# Sheet1.net
KiCad netlist of a schematic drawn in Altium Designer
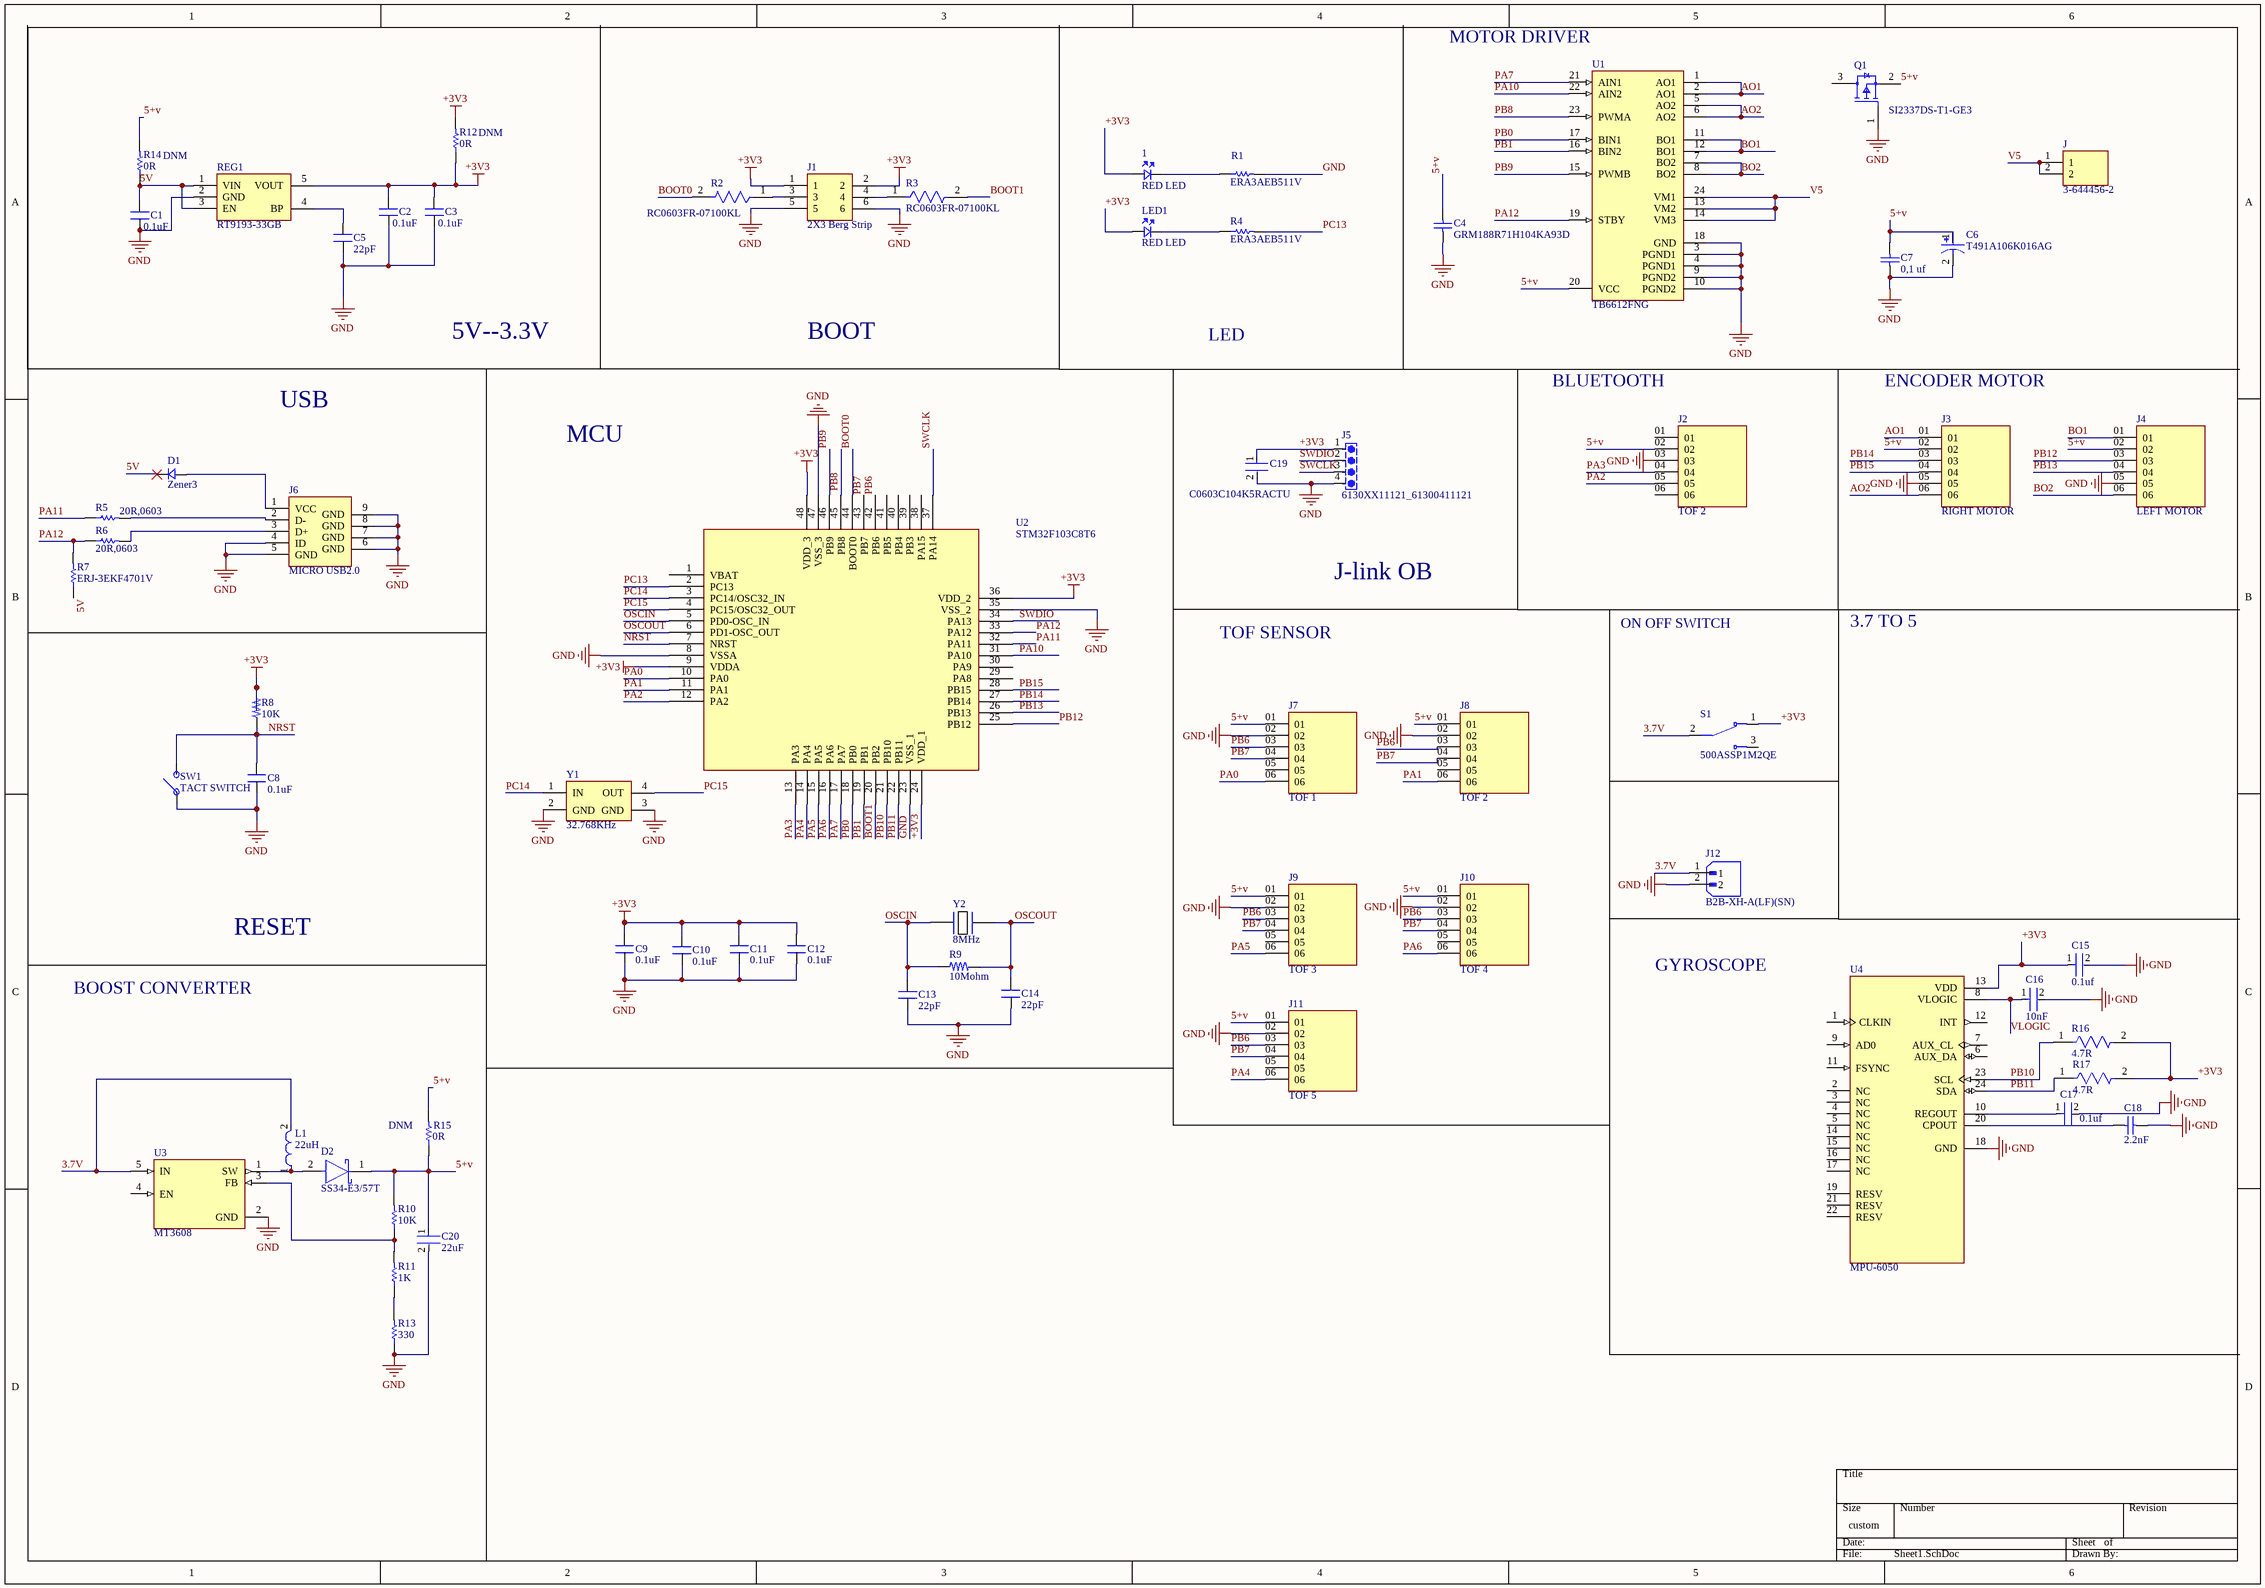
[diagram p0: Sheet1.SchDoc]

(export (version "E")
  (design (tool "Eeschema 10.0.6"))
  (components
    (comp (ref "1")
      (value "RED LED")
      (footprint "LED_0805")
      (description "Red 621nm LED Indication - Discrete 2V 0805 (2012 Metric)")
      (fields
        (field (name "MANUFACTURER") "Lite-On Inc.")
        (field (name "MANUFACTURER PART NUMBER") "LTST-C170EKT")
      )
      (libsource (lib "Schlib1") (part "LED-RED_10mA-0805"))
    )
    (comp (ref "C1")
      (value "0.1uF")
      (footprint "CAP_0805")
      (description "0.1µF ±5% 50V Ceramic Capacitor X7R 0805 (2012 Metric)")
      (fields
        (field (name "MANUFACTURER") "KEMET")
        (field (name "MANUFACTURING PART NUMBER") "C0805C104J5RACTU")
      )
      (libsource (lib "Schlib1") (part "CAP_0.1uF-50V-5%-0805"))
    )
    (comp (ref "C2")
      (value "0.1uF")
      (footprint "CAP_0805")
      (description "0.1µF ±5% 50V Ceramic Capacitor X7R 0805 (2012 Metric)")
      (fields
        (field (name "MANUFACTURER") "KEMET")
        (field (name "MANUFACTURING PART NUMBER") "C0805C104J5RACTU")
      )
      (libsource (lib "Schlib1") (part "CAP_0.1uF-50V-5%-0805"))
    )
    (comp (ref "C3")
      (value "0.1uF")
      (footprint "CAP_0805")
      (description "0.1µF ±5% 50V Ceramic Capacitor X7R 0805 (2012 Metric)")
      (fields
        (field (name "MANUFACTURER") "KEMET")
        (field (name "MANUFACTURING PART NUMBER") "C0805C104J5RACTU")
      )
      (libsource (lib "Schlib1") (part "CAP_0.1uF-50V-5%-0805"))
    )
    (comp (ref "C4")
      (value "GRM188R71H104KA93D")
      (footprint "CAPC1608X90X35ML10T15")
      (description "Chip Capacitor, 0.1 uF, +/- 10%, 50 V, -55 to 125 degC, 0603 (1608 Metric), RoHS, Tape and Reel")
      (fields (field (name "TOLERANCE") "10%") (field (name "VOLTAGE") "50V"))
      (libsource (lib "Altium Content Vault") (part "CAP-NP-2"))
    )
    (comp (ref "C5")
      (value "22pF")
      (footprint "CAP_0805")
      (description "22pF ±5% 50V Ceramic Capacitor C0G, NP0 0805 (2012 Metric)")
      (fields
        (field (name "MANUFACTURER") "KEMET")
        (field (name "MANUFACTURER PART NUMBER") "C0805C220J5GACTU")
      )
      (libsource (lib "Schlib1") (part "CAP_22pF-50V-5%-0805"))
    )
    (comp (ref "C6")
      (value "T491A106K016AG")
      (footprint "CAPMP3216X180N")
      (description "10ÂµF Molded Tantalum Capacitors 16V 1206 (3216 Metric) 3Ohm")
      (fields (field (name "MF") "KEMET"))
      (libsource (lib "T491A106K016AG") (part "T491A106K016AG"))
    )
    (comp (ref "C7")
      (value "0,1 uf")
      (footprint "CAPC1608X90X35ML10T15")
      (description "Chip Capacitor, 0.1 uF, +/- 10%, 50 V, -55 to 125 degC, 0603 (1608 Metric), RoHS, Tape and Reel")
      (fields (field (name "TOLERANCE") "10%") (field (name "VOLTAGE") "50V"))
      (libsource (lib "Altium Content Vault") (part "CAP-NP-2"))
    )
    (comp (ref "C8")
      (value "0.1uF")
      (footprint "CAP_0805")
      (description "0.1µF ±5% 50V Ceramic Capacitor X7R 0805 (2012 Metric)")
      (fields
        (field (name "MANUFACTURER") "KEMET")
        (field (name "MANUFACTURING PART NUMBER") "C0805C104J5RACTU")
      )
      (libsource (lib "Schlib1") (part "CAP_0.1uF-50V-5%-0805"))
    )
    (comp (ref "C9")
      (value "0.1uF")
      (footprint "CAP_0805")
      (description "0.1µF ±5% 50V Ceramic Capacitor X7R 0805 (2012 Metric)")
      (fields
        (field (name "MANUFACTURER") "KEMET")
        (field (name "MANUFACTURING PART NUMBER") "C0805C104J5RACTU")
      )
      (libsource (lib "Schlib1") (part "CAP_0.1uF-50V-5%-0805"))
    )
    (comp (ref "C10")
      (value "0.1uF")
      (footprint "CAP_0805")
      (description "0.1µF ±5% 50V Ceramic Capacitor X7R 0805 (2012 Metric)")
      (fields
        (field (name "MANUFACTURER") "KEMET")
        (field (name "MANUFACTURING PART NUMBER") "C0805C104J5RACTU")
      )
      (libsource (lib "Schlib1") (part "CAP_0.1uF-50V-5%-0805"))
    )
    (comp (ref "C11")
      (value "0.1uF")
      (footprint "CAP_0805")
      (description "0.1µF ±5% 50V Ceramic Capacitor X7R 0805 (2012 Metric)")
      (fields
        (field (name "MANUFACTURER") "KEMET")
        (field (name "MANUFACTURING PART NUMBER") "C0805C104J5RACTU")
      )
      (libsource (lib "Schlib1") (part "CAP_0.1uF-50V-5%-0805"))
    )
    (comp (ref "C12")
      (value "0.1uF")
      (footprint "CAP_0805")
      (description "0.1µF ±5% 50V Ceramic Capacitor X7R 0805 (2012 Metric)")
      (fields
        (field (name "MANUFACTURER") "KEMET")
        (field (name "MANUFACTURING PART NUMBER") "C0805C104J5RACTU")
      )
      (libsource (lib "Schlib1") (part "CAP_0.1uF-50V-5%-0805"))
    )
    (comp (ref "C13")
      (value "22pF")
      (footprint "CAP_0805")
      (description "22pF ±5% 50V Ceramic Capacitor C0G, NP0 0805 (2012 Metric)")
      (fields
        (field (name "MANUFACTURER") "KEMET")
        (field (name "MANUFACTURER PART NUMBER") "C0805C220J5GACTU")
      )
      (libsource (lib "Schlib1") (part "CAP_22pF-50V-5%-0805"))
    )
    (comp (ref "C14")
      (value "22pF")
      (footprint "CAP_0805")
      (description "22pF ±5% 50V Ceramic Capacitor C0G, NP0 0805 (2012 Metric)")
      (fields
        (field (name "MANUFACTURER") "KEMET")
        (field (name "MANUFACTURER PART NUMBER") "C0805C220J5GACTU")
      )
      (libsource (lib "Schlib1") (part "CAP_22pF-50V-5%-0805"))
    )
    (comp (ref "C15")
      (value "0.1uf")
      (footprint "FP-C0402-BB-MFG")
      (description "CAP CER 0.1UF 16V X7R 0402")
      (fields
        (field (name "TOLERANCE") "0.1")
        (field (name "OCTOPART") "https://octopart.com/c0402c104k4ractu-kemet-94158")
      )
      (libsource (lib "Altium Content Vault") (part "b4654b650e69147ec39a6b967a45e02"))
    )
    (comp (ref "C16")
      (value "10nF")
      (footprint "FP-C0805C-DN-MFG")
      (description "CAP CER 10000PF 200V X7R 0805")
      (fields
        (field (name "OCTOPART") "https://octopart.com/c0805c103k2ractu-kemet-9138347")
        (field (name "MANUFACTURER PART NUMBER") "C0805C103K2RACTU")
      )
      (libsource (lib "Altium Content Vault") (part "b4654b650e69147ec39a6b967a45e02"))
    )
    (comp (ref "C17")
      (value "0.1uf")
      (footprint "FP-C0402-BB-MFG")
      (description "CAP CER 0.1UF 16V X7R 0402")
      (fields
        (field (name "TOLERANCE") "0.1")
        (field (name "OCTOPART") "https://octopart.com/c0402c104k4ractu-kemet-94158")
      )
      (libsource (lib "Altium Content Vault") (part "b4654b650e69147ec39a6b967a45e02"))
    )
    (comp (ref "C18")
      (value "2.2nF")
      (footprint "CAPC2013X94X50LL20T25")
      (fields
        (field (name "PART NUMBER") "08051C222JAT2A")
        (field (name "MANUFACTURER") "AVX Interconnect / Elco")
      )
      (libsource (lib "Altium Content Vault") (part "CAP"))
    )
    (comp (ref "C19")
      (value "C0603C104K5RACTU")
      (footprint "FP-C0603C-CF-MFG")
      (description "CAP CER 0.1UF 50V X7R 0603")
      (fields (field (name "TOLERANCE") "0.1") (field (name "MANUFACTURER") "KEMET"))
      (libsource (lib "Altium Content Vault") (part "b4654b650e69147ec39a6b967a45e02"))
    )
    (comp (ref "C20")
      (value "22uF")
      (footprint "FP-GRM21B-0_15-MFG")
      (description "Chip Multilayer Ceramic Capacitors for General Purpose, 0805, 22uF, X5R, 15%, 20%, 6.3V")
      (fields (field (name "VOLTAGE") "6.3V") (field (name "TOLERANCE") "20%"))
      (libsource (lib "Altium Content Vault") (part "b4654b650e69147ec39a6b967a45e02"))
    )
    (comp (ref "D1")
      (value "Zener3")
      (footprint "DIO_SOD80C")
      (description "Zener Diode 3.3V 500mW ±5% Surface Mount LLDS; MiniMelf")
      (fields
        (field (name "MANUFACTURER") "Nexperia USA Inc.")
        (field (name "MANUFACTURING PART NUMBER") "BZV55-C3V3,115")
      )
      (libsource (lib "Schlib1") (part "DIO-Z_3.3V-0.5W-SOD80C"))
    )
    (comp (ref "D2")
      (value "SS34-E3/57T")
      (footprint "FP-95402-MFG")
      (description "DIODE SCHOTTKY 40V 3A DO214AB")
      (fields
        (field (name "MANUFACTURER") "Vishay")
        (field (name "OCTOPART") "https://octopart.com/ss34-e3%2F57t-vishay-39552907")
      )
      (libsource (lib "Altium Content Vault") (part "1d6ec82d83fb6aee721767c19dac4b9"))
    )
    (comp (ref "J")
      (value "3-644456-2")
      (footprint "TE_3-644456-2")
      (description "Connector Unshrouded Header HDR 2 Position 2.54mm Solder Straight Thru-Hole")
      (fields (field (name "DIGI-KEY_PART_NUMBER") "A31112-ND") (field (name "MF") "TE Connectivity"))
      (libsource (lib "3-644456-2") (part "3-644456-2"))
    )
    (comp (ref "J1")
      (value "2X3 Berg Strip")
      (footprint "CON6_100_59D78_TH_ST_Duplicate")
      (description "6 pin, 2 row, 2.54mm pitch bergstrip")
      (fields (field (name "MANUFACTURER") "NA"))
      (libsource (lib "Schlib1") (part "CON-BS-PLG_2X3-100-TH-ST"))
    )
    (comp (ref "J2")
      (value "TOF 2")
      (footprint "SAMTEC_MTSW-106-22-S-S-360")
      (fields (field (name "MP") "MTSW-106-22-S-S-360"))
      (libsource (lib "MTSW-106-22-S-S-360") (part "MTSW-106-22-S-S-360"))
    )
    (comp (ref "J3")
      (value "RIGHT MOTOR")
      (footprint "SAMTEC_MTSW-106-22-S-S-360")
      (fields (field (name "MP") "MTSW-106-22-S-S-360"))
      (libsource (lib "MTSW-106-22-S-S-360") (part "MTSW-106-22-S-S-360"))
    )
    (comp (ref "J4")
      (value "LEFT MOTOR")
      (footprint "SAMTEC_MTSW-106-22-S-S-360")
      (fields (field (name "MP") "MTSW-106-22-S-S-360"))
      (libsource (lib "MTSW-106-22-S-S-360") (part "MTSW-106-22-S-S-360"))
    )
    (comp (ref "J5")
      (value "6130XX11121_61300411121")
      (footprint "61300411121")
      (description "4 pins, 1 row, straight, gold plating")
      (fields (field (name "MF") "Wurth Electronics") (field (name "MP") "61300411121"))
      (libsource (lib "6130XX11121_61300411121") (part "6130XX11121_61300411121"))
    )
    (comp (ref "J6")
      (value "MICRO USB2.0")
      (footprint "CON_10118192-0001LF_SMD")
      (description "USB - micro B USB 2.0 Receptacle Connector 5 Position Surface Mount, Right Angle")
      (fields
        (field (name "MANUFACTURER") "Amphenol ICC (FCI)")
        (field (name "MANUFACTURING PART NUMBER") "10118192-0002LF")
      )
      (libsource (lib "Schlib1") (part "CON-USB_10118192-0002LF-SMD"))
    )
    (comp (ref "J7")
      (value "TOF 1")
      (footprint "SAMTEC_MTSW-106-22-S-S-360")
      (fields (field (name "MP") "MTSW-106-22-S-S-360"))
      (libsource (lib "MTSW-106-22-S-S-360") (part "MTSW-106-22-S-S-360"))
    )
    (comp (ref "J8")
      (value "TOF 2")
      (footprint "SAMTEC_MTSW-106-22-S-S-360")
      (fields (field (name "MP") "MTSW-106-22-S-S-360"))
      (libsource (lib "MTSW-106-22-S-S-360") (part "MTSW-106-22-S-S-360"))
    )
    (comp (ref "J9")
      (value "TOF 3")
      (footprint "SAMTEC_MTSW-106-22-S-S-360")
      (fields (field (name "MP") "MTSW-106-22-S-S-360"))
      (libsource (lib "MTSW-106-22-S-S-360") (part "MTSW-106-22-S-S-360"))
    )
    (comp (ref "J10")
      (value "TOF 4")
      (footprint "SAMTEC_MTSW-106-22-S-S-360")
      (fields (field (name "MP") "MTSW-106-22-S-S-360"))
      (libsource (lib "MTSW-106-22-S-S-360") (part "MTSW-106-22-S-S-360"))
    )
    (comp (ref "J11")
      (value "TOF 5")
      (footprint "SAMTEC_MTSW-106-22-S-S-360")
      (fields (field (name "MP") "MTSW-106-22-S-S-360"))
      (libsource (lib "MTSW-106-22-S-S-360") (part "MTSW-106-22-S-S-360"))
    )
    (comp (ref "J12")
      (value "B2B-XH-A(LF)(SN)")
      (footprint "JST_B2B-XH-A(LF)(SN)")
      (description "Connector Header Through Hole 2 position 0.098 (2.50mm)")
      (fields (field (name "MF") "JST Sales America Inc."))
      (libsource (lib "B2B-XH-A_LF__SN_") (part "B2B-XH-A(LF)(SN)"))
    )
    (comp (ref "L1")
      (value "22uH")
      (footprint "FP-NR6045-MFG")
      (description "Shielded Wirewound Inductor 22uH 20% 1.5A 0.1495Ω SMD")
      (fields (field (name "TOLERANCE") "20%"))
      (libsource (lib "Altium Content Vault") (part "725321dda6339637d4d059423bc1c3c"))
    )
    (comp (ref "LED1")
      (value "RED LED")
      (footprint "LED_0805")
      (description "Red 621nm LED Indication - Discrete 2V 0805 (2012 Metric)")
      (fields
        (field (name "MANUFACTURER") "Lite-On Inc.")
        (field (name "MANUFACTURER PART NUMBER") "LTST-C170EKT")
      )
      (libsource (lib "Schlib1") (part "LED-RED_10mA-0805"))
    )
    (comp (ref "Q1")
      (value "SI2337DS-T1-GE3")
      (footprint "FP-S-03946-IPC_A")
      (description "MOSFET P-CH 80V 2.2A SOT23-3")
      (libsource (lib "Altium Content Vault") (part "712687b58a63c2867a75c2d2256a34e"))
    )
    (comp (ref "R1")
      (value "ERA3AEB511V")
      (footprint "RESC1608X55X30ML20T20")
      (fields (field (name "MANUFACTURER") "Panasonic"))
      (libsource (lib "Altium Content Vault") (part "RES"))
    )
    (comp (ref "R2")
      (value "RC0603FR-07100KL")
      (footprint "FP-RC0603-0_55-MFG")
      (description "RES SMD 100K OHM 1% 1/10W 0603")
      (fields (field (name "TOLERANCE") "1%"))
      (libsource (lib "Altium Content Vault") (part "1029c3af85768c4190bb7ad29bc67b5"))
    )
    (comp (ref "R3")
      (value "RC0603FR-07100KL")
      (footprint "FP-RC0603-0_55-MFG")
      (description "RES SMD 100K OHM 1% 1/10W 0603")
      (fields (field (name "TOLERANCE") "1%"))
      (libsource (lib "Altium Content Vault") (part "1029c3af85768c4190bb7ad29bc67b5"))
    )
    (comp (ref "R4")
      (value "ERA3AEB511V")
      (footprint "RESC1608X55X30ML20T20")
      (fields (field (name "MANUFACTURER") "Panasonic"))
      (libsource (lib "Altium Content Vault") (part "RES"))
    )
    (comp (ref "R5")
      (value "20R,0603")
      (footprint "RESC1609X55X30ML10T20")
      (fields (field (name "MANUFACTURER") "Vishay Dale") (field (name "PART NUMBER") "TNPW060320R0BEEA"))
      (libsource (lib "Altium Content Vault") (part "RES"))
    )
    (comp (ref "R6")
      (value "20R,0603")
      (footprint "RESC1609X55X30ML10T20")
      (fields (field (name "MANUFACTURER") "Vishay Dale") (field (name "PART NUMBER") "TNPW060320R0BEEA"))
      (libsource (lib "Altium Content Vault") (part "RES"))
    )
    (comp (ref "R7")
      (value "ERJ-3EKF4701V")
      (footprint "RESC1608X55X30NL15T15")
      (fields (field (name "TOLERANCE") "5%"))
      (libsource (lib "Altium Content Vault") (part "RES-2"))
    )
    (comp (ref "R8")
      (value "10K")
      (footprint "RES_0805")
      (description "10 kOhms ±1% 0.125W, 1/8W Chip Resistor 0805 (2012 Metric) Moisture Resistant Thick Film")
      (fields
        (field (name "MANUFACTURER") "Yageo")
        (field (name "MANUFACTURING PART NUMBER") "RC0805FR-0710KL")
      )
      (libsource (lib "Schlib1") (part "RES_10K-0.125W-1%-0805"))
    )
    (comp (ref "R9")
      (value "10Mohm")
      (footprint "RES_0805")
      (fields
        (field (name "MANUFACTURER") "Rohm Semiconductor")
        (field (name "MANUFACTURING PART NUMBER") "KTR10EZPF1005")
      )
      (libsource (lib "Schlib1") (part "RES_10MOHM-0.125W-1%-0805"))
    )
    (comp (ref "R10")
      (value "10K")
      (footprint "RESC1609X50X30NL8T20")
      (description "Chip Resistor, 10 KOhm, +/- 1%, 100 mW, -55 to 155 degC, 0603 (1608 Metric), RoHS, Tape and Reel")
      (fields (field (name "MANUFACTURER") "Vishay Semiconductor"))
      (libsource (lib "Altium Content Vault") (part "RES-2"))
    )
    (comp (ref "R11")
      (value "1K")
      (footprint "RESC3216X70X50LL05T20")
      (fields (field (name "MANUFACTURER") "Panasonic") (field (name "PART NUMBER") "ERJ-8ENF1001V"))
      (libsource (lib "Altium Content Vault") (part "RES"))
    )
    (comp (ref "R12")
      (value "0R")
      (footprint "RESC1608X55X25ML10T15")
      (description "Chip Resistor, 0 Ohm, +/- 5%, 0.1 W, -55 to 155 degC, 0603 (1608 Metric), RoHS, Tape and Reel")
      (fields (field (name "TOLERANCE") "5%") (field (name "MANUFACTURER") "Yageo"))
      (libsource (lib "Altium Content Vault") (part "RES-2"))
    )
    (comp (ref "R13")
      (value "330")
      (footprint "RESC2013X60X40LL20T25")
      (fields (field (name "MANUFACTURER") "Panasonic") (field (name "PART NUMBER") "ERA6AEB331V"))
      (libsource (lib "Altium Content Vault") (part "RES"))
    )
    (comp (ref "R14")
      (value "0R")
      (footprint "RESC1608X55X25ML10T15")
      (description "Chip Resistor, 0 Ohm, +/- 5%, 0.1 W, -55 to 155 degC, 0603 (1608 Metric), RoHS, Tape and Reel")
      (fields (field (name "TOLERANCE") "5%") (field (name "MANUFACTURER") "Yageo"))
      (libsource (lib "Altium Content Vault") (part "RES-2"))
    )
    (comp (ref "R15")
      (value "0R")
      (footprint "RESC1608X55X25ML10T15")
      (description "Chip Resistor, 0 Ohm, +/- 5%, 0.1 W, -55 to 155 degC, 0603 (1608 Metric), RoHS, Tape and Reel")
      (fields (field (name "TOLERANCE") "5%") (field (name "MANUFACTURER") "Yageo"))
      (libsource (lib "Altium Content Vault") (part "RES-2"))
    )
    (comp (ref "R16")
      (value "4.7R")
      (footprint "FP-RC0402-0_4-MFG")
      (fields (field (name "TOLERANCE") "5%"))
      (libsource (lib "Altium Content Vault") (part "RC0402JR-074K7L"))
    )
    (comp (ref "R17")
      (value "4.7R")
      (footprint "FP-RC0402-0_4-MFG")
      (fields (field (name "TOLERANCE") "5%"))
      (libsource (lib "Altium Content Vault") (part "RC0402JR-074K7L"))
    )
    (comp (ref "REG1")
      (value "RT9193-33GB")
      (footprint "SOT23-5")
      (description "Linear Voltage Regulator IC 1 Output 300mA SOT-23-5")
      (fields (field (name "MANUFACTURER") "Richtek USA Inc."))
      (libsource (lib "Schlib1") (part "REG_3.3V-5.5V-0.3A-SOT-23-5"))
    )
    (comp (ref "S1")
      (value "500ASSP1M2QE")
      (footprint "SW_500ASSP1M2QE")
      (description "1P2T Sub-miniature Slide Switch")
      (fields (field (name "MF") "E-Switch"))
      (libsource (lib "500ASSP1M2QE") (part "500ASSP1M2QE"))
    )
    (comp (ref "SW1")
      (value "TACT SWITCH")
      (footprint "SW_342_SMD")
      (description "Tactile Switch SPST-NO Top Actuated Surface Mount")
      (fields (field (name "MANUFACTURER") "C&K") (field (name "MANUFACTURING PART NUMBER") "KSR223GLFG"))
      (libsource (lib "Schlib1") (part "SW_KSR223GLFG-SMD"))
    )
    (comp (ref "U1")
      (value "TB6612FNG")
      (footprint "TOSH-SSOP-24_M")
      (description "Driver IC for Dual DC Motor, 15 V, -20 to 85 degC, 24-Pin SSOP, RoHS, Tape and Reel")
      (libsource (lib "Altium Content Vault") (part "TOSH-TB6612FNG-SOP-24"))
    )
    (comp (ref "U2")
      (value "STM32F103C8T6")
      (footprint "LQFP-48_19.6_393_58X11_SMD")
      (description "ARM® Cortex®-M3 STM32F1 Microcontroller IC 32-Bit 72MHz 64KB (64K x 8) FLASH")
      (fields (field (name "MANUFACTURER") "STMicroelectronics"))
      (libsource (lib "Schlib1") (part "IC-STM32F103C8T6 _1"))
    )
    (comp (ref "U3")
      (value "MT3608")
      (footprint "SOT95P280X145-6N")
      (description "High Efficiency 1.2MHz2A Step Up Converter")
      (fields (field (name "MF") "Aerosemi Technology Co., Ltd"))
      (libsource (lib "MT3608") (part "MT3608"))
    )
    (comp (ref "U4")
      (value "MPU-6050")
      (footprint "QFN50P400X400X95-24N")
      (description "MPU-6050 series Accelerometer, Gyroscope, 3 Axis Sensor Evaluation Board")
      (fields (field (name "MF") "TDK InvenSense"))
      (libsource (lib "MPU-6050") (part "MPU-6050"))
    )
    (comp (ref "Y1")
      (value "32.768KHz")
      (footprint "XTAL_MC-405 32.7680K-G3")
      (description "Crystals SMD AT XTL MHZ +/-50PPM 12.5 PF 250 T/R")
      (fields
        (field (name "MANUFACTURER") "Epson")
        (field (name "MANUFACTURING PART NUMBER") "MC-405 32.7680K-G3: ROHS")
      )
      (libsource (lib "Schlib1") (part "XTAL_32.768KHz-MC-405 32.7680K-G3"))
    )
    (comp (ref "Y2")
      (value "8MHz")
      (footprint "XTAL_314_240X47_SMD")
      (description "Crystals 8MHz 22pF -20C 70C")
      (fields
        (field (name "MANUFACTURER") "IQD Frequency Products")
        (field (name "MANUFACTURING PART NUMBER") "LFXTAL030234Reel")
      )
      (libsource (lib "Schlib1") (part "XTAL_8MHZ-LFXTAL030234"))
    )
  )
  (nets
    (net (code "1") (name "+3V3") (class "Default")
      (node (ref "1") (pin "A") (pinfunction "A_A") (pintype "passive"))
      (node (ref "C10") (pin "1") (pinfunction "1_1") (pintype "passive"))
      (node (ref "C11") (pin "1") (pinfunction "1_1") (pintype "passive"))
      (node (ref "C12") (pin "1") (pinfunction "1_1") (pintype "passive"))
      (node (ref "C15") (pin "1") (pinfunction "1_1") (pintype "passive"))
      (node (ref "C19") (pin "1") (pinfunction "1_1") (pintype "passive"))
      (node (ref "C2") (pin "1") (pinfunction "1_1") (pintype "passive"))
      (node (ref "C3") (pin "1") (pinfunction "1_1") (pintype "passive"))
      (node (ref "C9") (pin "1") (pinfunction "1_1") (pintype "passive"))
      (node (ref "J1") (pin "1") (pinfunction "1_1") (pintype "passive"))
      (node (ref "J1") (pin "2") (pinfunction "2_2") (pintype "passive"))
      (node (ref "J5") (pin "1") (pinfunction "1_1") (pintype "passive"))
      (node (ref "LED1") (pin "A") (pinfunction "A_A") (pintype "passive"))
      (node (ref "R12") (pin "1") (pinfunction "1_1") (pintype "passive"))
      (node (ref "R12") (pin "2") (pinfunction "2_2") (pintype "passive"))
      (node (ref "R16") (pin "2") (pinfunction "2_2") (pintype "passive"))
      (node (ref "R17") (pin "2") (pinfunction "2_2") (pintype "passive"))
      (node (ref "R8") (pin "2") (pinfunction "2_2") (pintype "passive"))
      (node (ref "REG1") (pin "5") (pinfunction "VOUT_5") (pintype "passive"))
      (node (ref "S1") (pin "1") (pinfunction "1_1") (pintype "passive"))
      (node (ref "U2") (pin "24") (pinfunction "VDD_1_24") (pintype "passive"))
      (node (ref "U2") (pin "36") (pinfunction "VDD_2_36") (pintype "passive"))
      (node (ref "U2") (pin "48") (pinfunction "VDD_3_48") (pintype "passive"))
      (node (ref "U2") (pin "9") (pinfunction "VDDA_9") (pintype "passive"))
      (node (ref "U4") (pin "13") (pinfunction "VDD_13") (pintype "power_in"))
    )
    (net (code "2") (name "/3.7V") (class "Default")
      (node (ref "J12") (pin "1") (pinfunction "1_1") (pintype "passive"))
      (node (ref "L1") (pin "2") (pinfunction "2_2") (pintype "passive"))
      (node (ref "S1") (pin "2") (pinfunction "2_2") (pintype "passive"))
      (node (ref "U3") (pin "5") (pinfunction "IN_5") (pintype "input"))
    )
    (net (code "3") (name "/5+v") (class "Default")
      (node (ref "C20") (pin "1") (pinfunction "1_1") (pintype "passive"))
      (node (ref "C4") (pin "2") (pinfunction "2_2") (pintype "passive"))
      (node (ref "C6") (pin "1") (pinfunction "1_1") (pintype "passive"))
      (node (ref "C7") (pin "2") (pinfunction "2_2") (pintype "passive"))
      (node (ref "D2") (pin "1") (pinfunction "C_1") (pintype "passive"))
      (node (ref "J10") (pin "01") (pinfunction "01_01") (pintype "passive"))
      (node (ref "J11") (pin "01") (pinfunction "01_01") (pintype "passive"))
      (node (ref "J2") (pin "02") (pinfunction "02_02") (pintype "passive"))
      (node (ref "J3") (pin "02") (pinfunction "02_02") (pintype "passive"))
      (node (ref "J4") (pin "02") (pinfunction "02_02") (pintype "passive"))
      (node (ref "J7") (pin "01") (pinfunction "01_01") (pintype "passive"))
      (node (ref "J8") (pin "01") (pinfunction "01_01") (pintype "passive"))
      (node (ref "J9") (pin "01") (pinfunction "01_01") (pintype "passive"))
      (node (ref "Q1") (pin "2") (pinfunction "S_2") (pintype "passive"))
      (node (ref "R10") (pin "2") (pinfunction "2_2") (pintype "passive"))
      (node (ref "R14") (pin "2") (pinfunction "2_2") (pintype "passive"))
      (node (ref "R15") (pin "1") (pinfunction "1_1") (pintype "passive"))
      (node (ref "R15") (pin "2") (pinfunction "2_2") (pintype "passive"))
      (node (ref "U1") (pin "20") (pinfunction "VCC_20") (pintype "power_in"))
    )
    (net (code "4") (name "/5V") (class "Default")
      (node (ref "C1") (pin "1") (pinfunction "1_1") (pintype "passive"))
      (node (ref "D1") (pin "K") (pinfunction "K_K") (pintype "passive"))
      (node (ref "R14") (pin "1") (pinfunction "1_1") (pintype "passive"))
      (node (ref "R7") (pin "1") (pinfunction "1_1") (pintype "passive"))
      (node (ref "REG1") (pin "1") (pinfunction "VIN_1") (pintype "passive"))
      (node (ref "REG1") (pin "3") (pinfunction "EN_3") (pintype "passive"))
    )
    (net (code "5") (name "/AO1") (class "Default")
      (node (ref "J3") (pin "01") (pinfunction "01_01") (pintype "passive"))
      (node (ref "U1") (pin "1") (pinfunction "AO1_1") (pintype "tri_state"))
      (node (ref "U1") (pin "2") (pinfunction "AO1_2") (pintype "tri_state"))
    )
    (net (code "6") (name "/AO2") (class "Default")
      (node (ref "J3") (pin "06") (pinfunction "06_06") (pintype "passive"))
      (node (ref "U1") (pin "5") (pinfunction "AO2_5") (pintype "tri_state"))
      (node (ref "U1") (pin "6") (pinfunction "AO2_6") (pintype "tri_state"))
    )
    (net (code "7") (name "/BO1") (class "Default")
      (node (ref "J4") (pin "01") (pinfunction "01_01") (pintype "passive"))
      (node (ref "U1") (pin "11") (pinfunction "BO1_11") (pintype "tri_state"))
      (node (ref "U1") (pin "12") (pinfunction "BO1_12") (pintype "tri_state"))
    )
    (net (code "8") (name "/BO2") (class "Default")
      (node (ref "J4") (pin "06") (pinfunction "06_06") (pintype "passive"))
      (node (ref "U1") (pin "7") (pinfunction "BO2_7") (pintype "tri_state"))
      (node (ref "U1") (pin "8") (pinfunction "BO2_8") (pintype "tri_state"))
    )
    (net (code "9") (name "/BOOT0") (class "Default")
      (node (ref "R2") (pin "2") (pinfunction "2_2") (pintype "passive"))
      (node (ref "U2") (pin "44") (pinfunction "BOOT0_44") (pintype "passive"))
    )
    (net (code "10") (name "/BOOT1") (class "Default")
      (node (ref "R3") (pin "2") (pinfunction "2_2") (pintype "passive"))
      (node (ref "U2") (pin "20") (pinfunction "PB2_20") (pintype "passive"))
    )
    (net (code "11") (name "/NRST") (class "Default")
      (node (ref "C8") (pin "1") (pinfunction "1_1") (pintype "passive"))
      (node (ref "R8") (pin "1") (pinfunction "1_1") (pintype "passive"))
      (node (ref "SW1") (pin "2") (pinfunction "2_2") (pintype "passive"))
      (node (ref "U2") (pin "7") (pinfunction "NRST_7") (pintype "passive"))
    )
    (net (code "12") (name "/OSCIN") (class "Default")
      (node (ref "C13") (pin "2") (pinfunction "2_2") (pintype "passive"))
      (node (ref "R9") (pin "1") (pinfunction "1_1") (pintype "passive"))
      (node (ref "U2") (pin "5") (pinfunction "PD0-OSC_IN_5") (pintype "passive"))
      (node (ref "Y2") (pin "1") (pinfunction "1_1") (pintype "passive"))
    )
    (net (code "13") (name "/OSCOUT") (class "Default")
      (node (ref "C14") (pin "2") (pinfunction "2_2") (pintype "passive"))
      (node (ref "R9") (pin "2") (pinfunction "2_2") (pintype "passive"))
      (node (ref "U2") (pin "6") (pinfunction "PD1-OSC_OUT_6") (pintype "passive"))
      (node (ref "Y2") (pin "2") (pinfunction "2_2") (pintype "passive"))
    )
    (net (code "14") (name "/PA0") (class "Default")
      (node (ref "J7") (pin "06") (pinfunction "06_06") (pintype "passive"))
      (node (ref "U2") (pin "10") (pinfunction "PA0_10") (pintype "passive"))
    )
    (net (code "15") (name "/PA1") (class "Default")
      (node (ref "J8") (pin "06") (pinfunction "06_06") (pintype "passive"))
      (node (ref "U2") (pin "11") (pinfunction "PA1_11") (pintype "passive"))
    )
    (net (code "16") (name "/PA2") (class "Default")
      (node (ref "J2") (pin "05") (pinfunction "05_05") (pintype "passive"))
      (node (ref "U2") (pin "12") (pinfunction "PA2_12") (pintype "passive"))
    )
    (net (code "17") (name "/PA3") (class "Default")
      (node (ref "J2") (pin "04") (pinfunction "04_04") (pintype "passive"))
      (node (ref "U2") (pin "13") (pinfunction "PA3_13") (pintype "passive"))
    )
    (net (code "18") (name "/PA4") (class "Default")
      (node (ref "J11") (pin "06") (pinfunction "06_06") (pintype "passive"))
      (node (ref "U2") (pin "14") (pinfunction "PA4_14") (pintype "passive"))
    )
    (net (code "19") (name "/PA5") (class "Default")
      (node (ref "J9") (pin "06") (pinfunction "06_06") (pintype "passive"))
      (node (ref "U2") (pin "15") (pinfunction "PA5_15") (pintype "passive"))
    )
    (net (code "20") (name "/PA6") (class "Default")
      (node (ref "J10") (pin "06") (pinfunction "06_06") (pintype "passive"))
      (node (ref "U2") (pin "16") (pinfunction "PA6_16") (pintype "passive"))
    )
    (net (code "21") (name "/PA7") (class "Default")
      (node (ref "U1") (pin "21") (pinfunction "AIN1_21") (pintype "input"))
      (node (ref "U2") (pin "17") (pinfunction "PA7_17") (pintype "passive"))
    )
    (net (code "22") (name "/PA10") (class "Default")
      (node (ref "U1") (pin "22") (pinfunction "AIN2_22") (pintype "input"))
      (node (ref "U2") (pin "31") (pinfunction "PA10_31") (pintype "passive"))
    )
    (net (code "23") (name "/PA11") (class "Default")
      (node (ref "R5") (pin "1") (pinfunction "1_1") (pintype "passive"))
      (node (ref "U2") (pin "32") (pinfunction "PA11_32") (pintype "passive"))
    )
    (net (code "24") (name "/PA12") (class "Default")
      (node (ref "R6") (pin "1") (pinfunction "1_1") (pintype "passive"))
      (node (ref "R7") (pin "2") (pinfunction "2_2") (pintype "passive"))
      (node (ref "U1") (pin "19") (pinfunction "STBY_19") (pintype "input"))
      (node (ref "U2") (pin "33") (pinfunction "PA12_33") (pintype "passive"))
    )
    (net (code "25") (name "/PB0") (class "Default")
      (node (ref "U1") (pin "17") (pinfunction "BIN1_17") (pintype "input"))
      (node (ref "U2") (pin "18") (pinfunction "PB0_18") (pintype "passive"))
    )
    (net (code "26") (name "/PB1") (class "Default")
      (node (ref "U1") (pin "16") (pinfunction "BIN2_16") (pintype "input"))
      (node (ref "U2") (pin "19") (pinfunction "PB1_19") (pintype "passive"))
    )
    (net (code "27") (name "/PB6") (class "Default")
      (node (ref "J10") (pin "03") (pinfunction "03_03") (pintype "passive"))
      (node (ref "J11") (pin "03") (pinfunction "03_03") (pintype "passive"))
      (node (ref "J7") (pin "03") (pinfunction "03_03") (pintype "passive"))
      (node (ref "J8") (pin "03") (pinfunction "03_03") (pintype "passive"))
      (node (ref "J9") (pin "03") (pinfunction "03_03") (pintype "passive"))
      (node (ref "U2") (pin "42") (pinfunction "PB6_42") (pintype "passive"))
    )
    (net (code "28") (name "/PB7") (class "Default")
      (node (ref "J10") (pin "04") (pinfunction "04_04") (pintype "passive"))
      (node (ref "J11") (pin "04") (pinfunction "04_04") (pintype "passive"))
      (node (ref "J7") (pin "04") (pinfunction "04_04") (pintype "passive"))
      (node (ref "J8") (pin "04") (pinfunction "04_04") (pintype "passive"))
      (node (ref "J9") (pin "04") (pinfunction "04_04") (pintype "passive"))
      (node (ref "U2") (pin "43") (pinfunction "PB7_43") (pintype "passive"))
    )
    (net (code "29") (name "/PB8") (class "Default")
      (node (ref "U1") (pin "23") (pinfunction "PWMA_23") (pintype "input"))
      (node (ref "U2") (pin "45") (pinfunction "PB8_45") (pintype "passive"))
    )
    (net (code "30") (name "/PB9") (class "Default")
      (node (ref "U1") (pin "15") (pinfunction "PWMB_15") (pintype "input"))
      (node (ref "U2") (pin "46") (pinfunction "PB9_46") (pintype "passive"))
    )
    (net (code "31") (name "/PB10") (class "Default")
      (node (ref "R16") (pin "1") (pinfunction "1_1") (pintype "passive"))
      (node (ref "U2") (pin "21") (pinfunction "PB10_21") (pintype "passive"))
      (node (ref "U4") (pin "23") (pinfunction "SCL_23") (pintype "input"))
    )
    (net (code "32") (name "/PB11") (class "Default")
      (node (ref "R17") (pin "1") (pinfunction "1_1") (pintype "passive"))
      (node (ref "U2") (pin "22") (pinfunction "PB11_22") (pintype "passive"))
      (node (ref "U4") (pin "24") (pinfunction "SDA_24") (pintype "bidirectional"))
    )
    (net (code "33") (name "/PB12") (class "Default")
      (node (ref "J4") (pin "03") (pinfunction "03_03") (pintype "passive"))
      (node (ref "U2") (pin "25") (pinfunction "PB12_25") (pintype "passive"))
    )
    (net (code "34") (name "/PB13") (class "Default")
      (node (ref "J4") (pin "04") (pinfunction "04_04") (pintype "passive"))
      (node (ref "U2") (pin "26") (pinfunction "PB13_26") (pintype "passive"))
    )
    (net (code "35") (name "/PB14") (class "Default")
      (node (ref "J3") (pin "03") (pinfunction "03_03") (pintype "passive"))
      (node (ref "U2") (pin "27") (pinfunction "PB14_27") (pintype "passive"))
    )
    (net (code "36") (name "/PB15") (class "Default")
      (node (ref "J3") (pin "04") (pinfunction "04_04") (pintype "passive"))
      (node (ref "U2") (pin "28") (pinfunction "PB15_28") (pintype "passive"))
    )
    (net (code "37") (name "/PC13") (class "Default")
      (node (ref "R4") (pin "2") (pinfunction "2_2") (pintype "passive"))
      (node (ref "U2") (pin "2") (pinfunction "PC13_2") (pintype "passive"))
    )
    (net (code "38") (name "/PC14") (class "Default")
      (node (ref "U2") (pin "3") (pinfunction "PC14/OSC32_IN_3") (pintype "passive"))
      (node (ref "Y1") (pin "1") (pinfunction "IN_1") (pintype "passive"))
    )
    (net (code "39") (name "/PC15") (class "Default")
      (node (ref "U2") (pin "4") (pinfunction "PC15/OSC32_OUT_4") (pintype "passive"))
      (node (ref "Y1") (pin "4") (pinfunction "OUT_4") (pintype "passive"))
    )
    (net (code "40") (name "/SWCLK") (class "Default")
      (node (ref "J5") (pin "3") (pinfunction "3_3") (pintype "passive"))
      (node (ref "U2") (pin "37") (pinfunction "PA14_37") (pintype "passive"))
    )
    (net (code "41") (name "/SWDIO") (class "Default")
      (node (ref "J5") (pin "2") (pinfunction "2_2") (pintype "passive"))
      (node (ref "U2") (pin "34") (pinfunction "PA13_34") (pintype "passive"))
    )
    (net (code "42") (name "/V5") (class "Default")
      (node (ref "J") (pin "1") (pinfunction "1_1") (pintype "passive"))
      (node (ref "J") (pin "2") (pinfunction "2_2") (pintype "passive"))
      (node (ref "U1") (pin "13") (pinfunction "VM2_13") (pintype "power_in"))
      (node (ref "U1") (pin "14") (pinfunction "VM3_14") (pintype "power_in"))
      (node (ref "U1") (pin "24") (pinfunction "VM1_24") (pintype "power_in"))
    )
    (net (code "43") (name "/VLOGIC") (class "Default")
      (node (ref "C16") (pin "1") (pinfunction "1_1") (pintype "passive"))
      (node (ref "U4") (pin "8") (pinfunction "VLOGIC_8") (pintype "power_in"))
    )
    (net (code "44") (name "GND") (class "Default")
      (node (ref "C1") (pin "2") (pinfunction "2_2") (pintype "passive"))
      (node (ref "C10") (pin "2") (pinfunction "2_2") (pintype "passive"))
      (node (ref "C11") (pin "2") (pinfunction "2_2") (pintype "passive"))
      (node (ref "C12") (pin "2") (pinfunction "2_2") (pintype "passive"))
      (node (ref "C13") (pin "1") (pinfunction "1_1") (pintype "passive"))
      (node (ref "C14") (pin "1") (pinfunction "1_1") (pintype "passive"))
      (node (ref "C15") (pin "2") (pinfunction "2_2") (pintype "passive"))
      (node (ref "C16") (pin "2") (pinfunction "2_2") (pintype "passive"))
      (node (ref "C17") (pin "2") (pinfunction "2_2") (pintype "passive"))
      (node (ref "C18") (pin "2") (pinfunction "2_2") (pintype "passive"))
      (node (ref "C19") (pin "2") (pinfunction "2_2") (pintype "passive"))
      (node (ref "C2") (pin "2") (pinfunction "2_2") (pintype "passive"))
      (node (ref "C20") (pin "2") (pinfunction "2_2") (pintype "passive"))
      (node (ref "C3") (pin "2") (pinfunction "2_2") (pintype "passive"))
      (node (ref "C4") (pin "1") (pinfunction "1_1") (pintype "passive"))
      (node (ref "C5") (pin "1") (pinfunction "1_1") (pintype "passive"))
      (node (ref "C6") (pin "2") (pinfunction "2_2") (pintype "passive"))
      (node (ref "C7") (pin "1") (pinfunction "1_1") (pintype "passive"))
      (node (ref "C8") (pin "2") (pinfunction "2_2") (pintype "passive"))
      (node (ref "C9") (pin "2") (pinfunction "2_2") (pintype "passive"))
      (node (ref "J1") (pin "5") (pinfunction "5_5") (pintype "passive"))
      (node (ref "J1") (pin "6") (pinfunction "6_6") (pintype "passive"))
      (node (ref "J10") (pin "02") (pinfunction "02_02") (pintype "passive"))
      (node (ref "J11") (pin "02") (pinfunction "02_02") (pintype "passive"))
      (node (ref "J12") (pin "2") (pinfunction "2_2") (pintype "passive"))
      (node (ref "J2") (pin "03") (pinfunction "03_03") (pintype "passive"))
      (node (ref "J3") (pin "05") (pinfunction "05_05") (pintype "passive"))
      (node (ref "J4") (pin "05") (pinfunction "05_05") (pintype "passive"))
      (node (ref "J5") (pin "4") (pinfunction "4_4") (pintype "passive"))
      (node (ref "J6") (pin "4") (pinfunction "ID_4") (pintype "passive"))
      (node (ref "J6") (pin "5") (pinfunction "GND_5") (pintype "passive"))
      (node (ref "J6") (pin "6") (pinfunction "GND_6") (pintype "passive"))
      (node (ref "J6") (pin "7") (pinfunction "GND_7") (pintype "passive"))
      (node (ref "J6") (pin "8") (pinfunction "GND_8") (pintype "passive"))
      (node (ref "J6") (pin "9") (pinfunction "GND_9") (pintype "passive"))
      (node (ref "J7") (pin "02") (pinfunction "02_02") (pintype "passive"))
      (node (ref "J8") (pin "02") (pinfunction "02_02") (pintype "passive"))
      (node (ref "J9") (pin "02") (pinfunction "02_02") (pintype "passive"))
      (node (ref "Q1") (pin "1") (pinfunction "G_1") (pintype "passive"))
      (node (ref "R1") (pin "2") (pinfunction "2_2") (pintype "passive"))
      (node (ref "R13") (pin "1") (pinfunction "1_1") (pintype "passive"))
      (node (ref "REG1") (pin "2") (pinfunction "GND_2") (pintype "passive"))
      (node (ref "SW1") (pin "1") (pinfunction "1_1") (pintype "passive"))
      (node (ref "U1") (pin "10") (pinfunction "PGND2_10") (pintype "power_in"))
      (node (ref "U1") (pin "18") (pinfunction "GND_18") (pintype "power_in"))
      (node (ref "U1") (pin "3") (pinfunction "PGND1_3") (pintype "power_in"))
      (node (ref "U1") (pin "4") (pinfunction "PGND1_4") (pintype "power_in"))
      (node (ref "U1") (pin "9") (pinfunction "PGND2_9") (pintype "power_in"))
      (node (ref "U2") (pin "23") (pinfunction "VSS_1_23") (pintype "passive"))
      (node (ref "U2") (pin "35") (pinfunction "VSS_2_35") (pintype "passive"))
      (node (ref "U2") (pin "47") (pinfunction "VSS_3_47") (pintype "passive"))
      (node (ref "U2") (pin "8") (pinfunction "VSSA_8") (pintype "passive"))
      (node (ref "U3") (pin "2") (pinfunction "GND_2") (pintype "power_in"))
      (node (ref "U4") (pin "18") (pinfunction "GND_18") (pintype "power_in"))
      (node (ref "Y1") (pin "2") (pinfunction "GND_2") (pintype "passive"))
      (node (ref "Y1") (pin "3") (pinfunction "GND_3") (pintype "passive"))
    )
    (net (code "45") (name "Net-(1-PadK)") (class "Default")
      (node (ref "1") (pin "K") (pinfunction "K_K") (pintype "passive"))
      (node (ref "R1") (pin "1") (pinfunction "1_1") (pintype "passive"))
    )
    (net (code "46") (name "Net-(D2-A)") (class "Default")
      (node (ref "D2") (pin "2") (pinfunction "A_2") (pintype "passive"))
      (node (ref "L1") (pin "1") (pinfunction "1_1") (pintype "passive"))
      (node (ref "U3") (pin "1") (pinfunction "SW_1") (pintype "output"))
    )
    (net (code "47") (name "Net-(J1-Pad3)") (class "Default")
      (node (ref "J1") (pin "3") (pinfunction "3_3") (pintype "passive"))
      (node (ref "R2") (pin "1") (pinfunction "1_1") (pintype "passive"))
    )
    (net (code "48") (name "Net-(J1-Pad4)") (class "Default")
      (node (ref "J1") (pin "4") (pinfunction "4_4") (pintype "passive"))
      (node (ref "R3") (pin "1") (pinfunction "1_1") (pintype "passive"))
    )
    (net (code "49") (name "Net-(J6-D+)") (class "Default")
      (node (ref "J6") (pin "3") (pinfunction "D+_3") (pintype "passive"))
      (node (ref "R6") (pin "2") (pinfunction "2_2") (pintype "passive"))
    )
    (net (code "50") (name "Net-(J6-D-)") (class "Default")
      (node (ref "J6") (pin "2") (pinfunction "D-_2") (pintype "passive"))
      (node (ref "R5") (pin "2") (pinfunction "2_2") (pintype "passive"))
    )
    (net (code "51") (name "Net-(J6-VCC)") (class "Default")
      (node (ref "D1") (pin "A") (pinfunction "A_A") (pintype "passive"))
      (node (ref "J6") (pin "1") (pinfunction "VCC_1") (pintype "passive"))
    )
    (net (code "52") (name "Net-(LED1-PadK)") (class "Default")
      (node (ref "LED1") (pin "K") (pinfunction "K_K") (pintype "passive"))
      (node (ref "R4") (pin "1") (pinfunction "1_1") (pintype "passive"))
    )
    (net (code "53") (name "Net-(R11-Pad1)") (class "Default")
      (node (ref "R11") (pin "1") (pinfunction "1_1") (pintype "passive"))
      (node (ref "R13") (pin "2") (pinfunction "2_2") (pintype "passive"))
    )
    (net (code "54") (name "Net-(REG1-BP)") (class "Default")
      (node (ref "C5") (pin "2") (pinfunction "2_2") (pintype "passive"))
      (node (ref "REG1") (pin "4") (pinfunction "BP_4") (pintype "passive"))
    )
    (net (code "55") (name "Net-(U3-FB)") (class "Default")
      (node (ref "R10") (pin "1") (pinfunction "1_1") (pintype "passive"))
      (node (ref "R11") (pin "2") (pinfunction "2_2") (pintype "passive"))
      (node (ref "U3") (pin "3") (pinfunction "FB_3") (pintype "input"))
    )
    (net (code "56") (name "Net-(U4-CPOUT)") (class "Default")
      (node (ref "C18") (pin "1") (pinfunction "1_1") (pintype "passive"))
      (node (ref "U4") (pin "20") (pinfunction "CPOUT_20") (pintype "passive"))
    )
    (net (code "57") (name "Net-(U4-REGOUT)") (class "Default")
      (node (ref "C17") (pin "1") (pinfunction "1_1") (pintype "passive"))
      (node (ref "U4") (pin "10") (pinfunction "REGOUT_10") (pintype "passive"))
    )
    (net (code "58") (name "unconnected-(J2-Pad01)") (class "Default")
      (node (ref "J2") (pin "01") (pinfunction "01_01") (pintype "passive"))
    )
    (net (code "59") (name "unconnected-(J2-Pad06)") (class "Default")
      (node (ref "J2") (pin "06") (pinfunction "06_06") (pintype "passive"))
    )
    (net (code "60") (name "unconnected-(J7-Pad05)") (class "Default")
      (node (ref "J7") (pin "05") (pinfunction "05_05") (pintype "passive"))
    )
    (net (code "61") (name "unconnected-(J8-Pad05)") (class "Default")
      (node (ref "J8") (pin "05") (pinfunction "05_05") (pintype "passive"))
    )
    (net (code "62") (name "unconnected-(J9-Pad05)") (class "Default")
      (node (ref "J9") (pin "05") (pinfunction "05_05") (pintype "passive"))
    )
    (net (code "63") (name "unconnected-(J10-Pad05)") (class "Default")
      (node (ref "J10") (pin "05") (pinfunction "05_05") (pintype "passive"))
    )
    (net (code "64") (name "unconnected-(J11-Pad05)") (class "Default")
      (node (ref "J11") (pin "05") (pinfunction "05_05") (pintype "passive"))
    )
    (net (code "65") (name "unconnected-(Q1-D-Pad3)") (class "Default")
      (node (ref "Q1") (pin "3") (pinfunction "D_3") (pintype "passive"))
    )
    (net (code "66") (name "unconnected-(S1-Pad3)") (class "Default")
      (node (ref "S1") (pin "3") (pinfunction "3_3") (pintype "passive"))
    )
    (net (code "67") (name "unconnected-(U2-PA8-Pad29)") (class "Default")
      (node (ref "U2") (pin "29") (pinfunction "PA8_29") (pintype "passive"))
    )
    (net (code "68") (name "unconnected-(U2-PA9-Pad30)") (class "Default")
      (node (ref "U2") (pin "30") (pinfunction "PA9_30") (pintype "passive"))
    )
    (net (code "69") (name "unconnected-(U2-PA15-Pad38)") (class "Default")
      (node (ref "U2") (pin "38") (pinfunction "PA15_38") (pintype "passive"))
    )
    (net (code "70") (name "unconnected-(U2-PB3-Pad39)") (class "Default")
      (node (ref "U2") (pin "39") (pinfunction "PB3_39") (pintype "passive"))
    )
    (net (code "71") (name "unconnected-(U2-PB4-Pad40)") (class "Default")
      (node (ref "U2") (pin "40") (pinfunction "PB4_40") (pintype "passive"))
    )
    (net (code "72") (name "unconnected-(U2-PB5-Pad41)") (class "Default")
      (node (ref "U2") (pin "41") (pinfunction "PB5_41") (pintype "passive"))
    )
    (net (code "73") (name "unconnected-(U2-VBAT-Pad1)") (class "Default")
      (node (ref "U2") (pin "1") (pinfunction "VBAT_1") (pintype "passive"))
    )
    (net (code "74") (name "unconnected-(U3-EN-Pad4)") (class "Default")
      (node (ref "U3") (pin "4") (pinfunction "EN_4") (pintype "input"))
    )
    (net (code "75") (name "unconnected-(U4-AD0-Pad9)") (class "Default")
      (node (ref "U4") (pin "9") (pinfunction "AD0_9") (pintype "input"))
    )
    (net (code "76") (name "unconnected-(U4-AUX_CL-Pad7)") (class "Default")
      (node (ref "U4") (pin "7") (pinfunction "AUX_CL_7") (pintype "output"))
    )
    (net (code "77") (name "unconnected-(U4-AUX_DA-Pad6)") (class "Default")
      (node (ref "U4") (pin "6") (pinfunction "AUX_DA_6") (pintype "bidirectional"))
    )
    (net (code "78") (name "unconnected-(U4-CLKIN-Pad1)") (class "Default")
      (node (ref "U4") (pin "1") (pinfunction "CLKIN_1") (pintype "input"))
    )
    (net (code "79") (name "unconnected-(U4-FSYNC-Pad11)") (class "Default")
      (node (ref "U4") (pin "11") (pinfunction "FSYNC_11") (pintype "input"))
    )
    (net (code "80") (name "unconnected-(U4-INT-Pad12)") (class "Default")
      (node (ref "U4") (pin "12") (pinfunction "INT_12") (pintype "output"))
    )
    (net (code "81") (name "unconnected-(U4-NC-Pad2)") (class "Default")
      (node (ref "U4") (pin "2") (pinfunction "NC_2") (pintype "passive"))
    )
    (net (code "82") (name "unconnected-(U4-NC-Pad3)") (class "Default")
      (node (ref "U4") (pin "3") (pinfunction "NC_3") (pintype "passive"))
    )
    (net (code "83") (name "unconnected-(U4-NC-Pad4)") (class "Default")
      (node (ref "U4") (pin "4") (pinfunction "NC_4") (pintype "passive"))
    )
    (net (code "84") (name "unconnected-(U4-NC-Pad5)") (class "Default")
      (node (ref "U4") (pin "5") (pinfunction "NC_5") (pintype "passive"))
    )
    (net (code "85") (name "unconnected-(U4-NC-Pad14)") (class "Default")
      (node (ref "U4") (pin "14") (pinfunction "NC_14") (pintype "passive"))
    )
    (net (code "86") (name "unconnected-(U4-NC-Pad15)") (class "Default")
      (node (ref "U4") (pin "15") (pinfunction "NC_15") (pintype "passive"))
    )
    (net (code "87") (name "unconnected-(U4-NC-Pad16)") (class "Default")
      (node (ref "U4") (pin "16") (pinfunction "NC_16") (pintype "passive"))
    )
    (net (code "88") (name "unconnected-(U4-NC-Pad17)") (class "Default")
      (node (ref "U4") (pin "17") (pinfunction "NC_17") (pintype "passive"))
    )
    (net (code "89") (name "unconnected-(U4-RESV-Pad19)") (class "Default")
      (node (ref "U4") (pin "19") (pinfunction "RESV_19") (pintype "passive"))
    )
    (net (code "90") (name "unconnected-(U4-RESV-Pad21)") (class "Default")
      (node (ref "U4") (pin "21") (pinfunction "RESV_21") (pintype "passive"))
    )
    (net (code "91") (name "unconnected-(U4-RESV-Pad22)") (class "Default")
      (node (ref "U4") (pin "22") (pinfunction "RESV_22") (pintype "passive"))
    )
  )
)
